# MD029A_CSA.net
KiCad netlist of a schematic drawn in Altium Designer
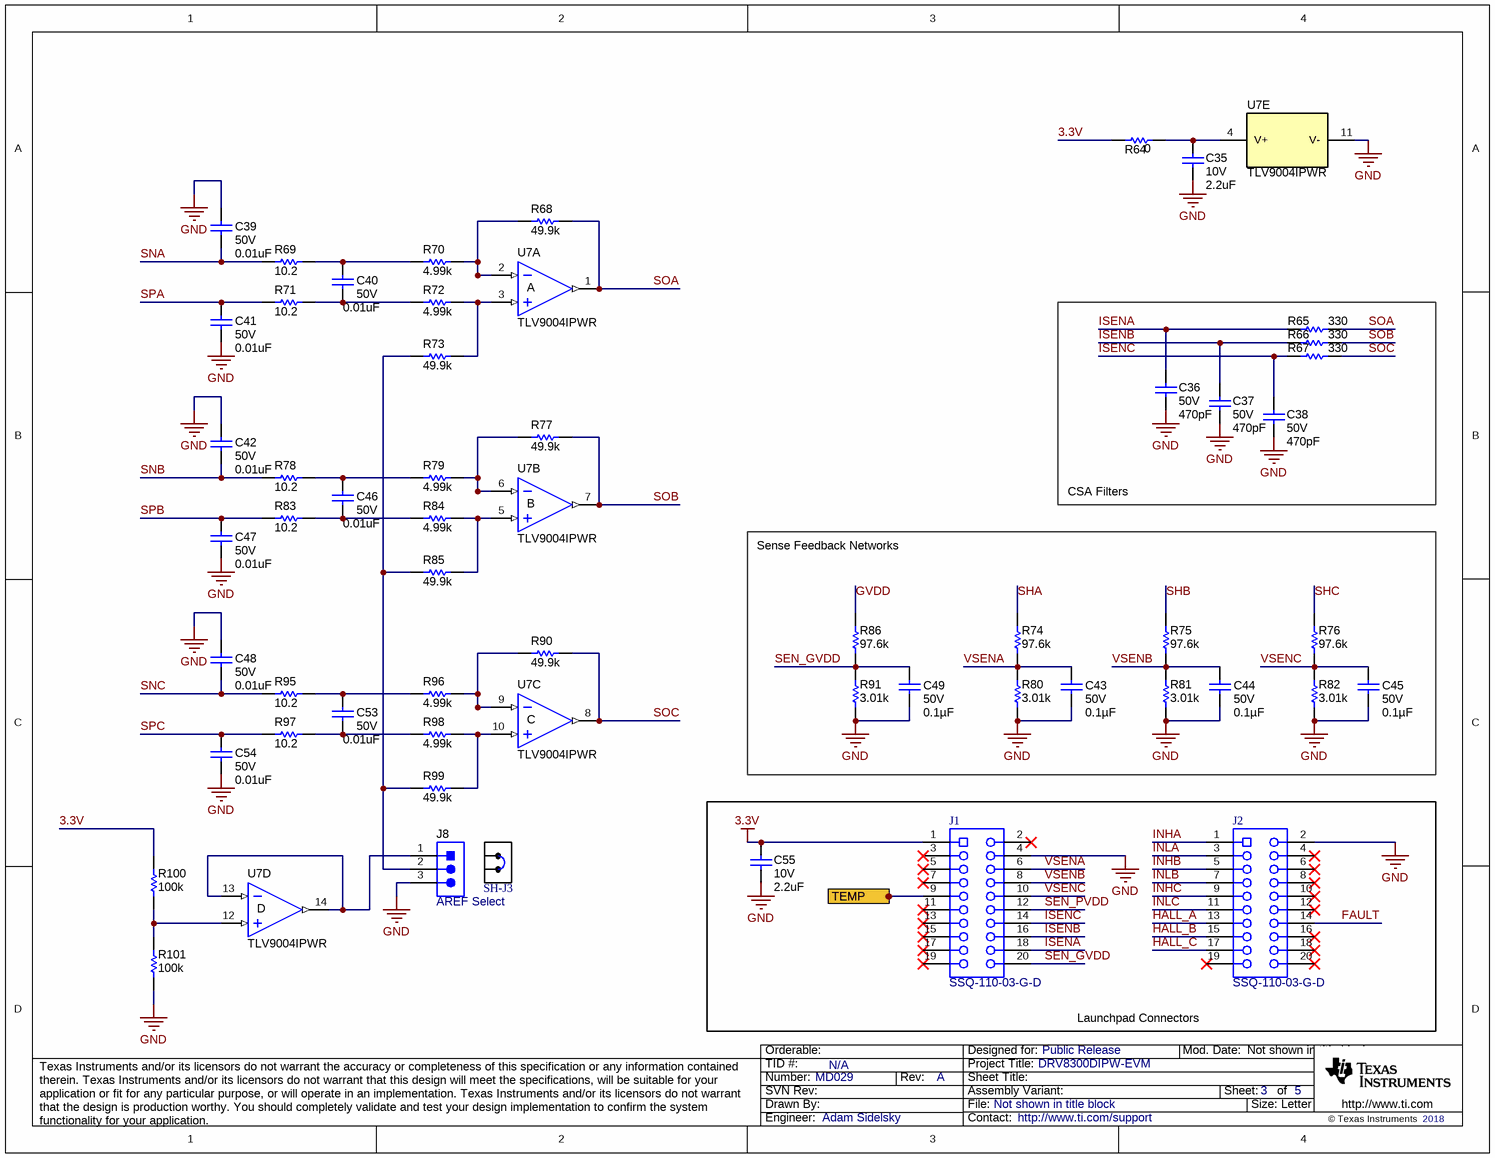
[diagram p0: MD029A_CSA.SchDoc]

(export (version "E")
  (design (tool "Eeschema 10.0.6"))
  (components
    (comp (ref "C35")
      (value "C1005X5R1A225K050BC")
      (footprint "0402L")
      (description "CAP, CERM, 2.2 uF, 10 V, +/- 10%, X5R, 0402")
      (fields
        (field (name "MANUFACTURER") "TDK")
        (field (name "VDC_V") "10V")
        (field (name "VALUEDISPLAYED") "2.2uF")
        (field (name "PUBLISHER") "Texas Instruments")
      )
      (libsource (lib "Altium Vault - TI") (part "Capacitor"))
    )
    (comp (ref "C36")
      (value "C0805C471K5RACTU")
      (footprint "0805L")
      (description "CAP, CERM, 470 pF, 50 V, +/- 10%, X7R, 0805")
      (fields
        (field (name "MANUFACTURER") "Kemet")
        (field (name "VDC_V") "50V")
        (field (name "VALUEDISPLAYED") "470pF")
        (field (name "PUBLISHER") "Texas Instruments")
      )
      (libsource (lib "Altium Vault - TI") (part "Capacitor"))
    )
    (comp (ref "C37")
      (value "C0805C471K5RACTU")
      (footprint "0805L")
      (description "CAP, CERM, 470 pF, 50 V, +/- 10%, X7R, 0805")
      (fields
        (field (name "MANUFACTURER") "Kemet")
        (field (name "VDC_V") "50V")
        (field (name "VALUEDISPLAYED") "470pF")
        (field (name "PUBLISHER") "Texas Instruments")
      )
      (libsource (lib "Altium Vault - TI") (part "Capacitor"))
    )
    (comp (ref "C38")
      (value "C0805C471K5RACTU")
      (footprint "0805L")
      (description "CAP, CERM, 470 pF, 50 V, +/- 10%, X7R, 0805")
      (fields
        (field (name "MANUFACTURER") "Kemet")
        (field (name "VDC_V") "50V")
        (field (name "VALUEDISPLAYED") "470pF")
        (field (name "PUBLISHER") "Texas Instruments")
      )
      (libsource (lib "Altium Vault - TI") (part "Capacitor"))
    )
    (comp (ref "C39")
      (value "GCM188R71H103KA37D")
      (footprint "0603L")
      (description "CAP, CERM, 0.01 uF, 50 V, +/- 10%, X7R, AEC-Q200 Grade 1, 0603")
      (fields
        (field (name "MANUFACTURER") "MuRata")
        (field (name "VDC_V") "50V")
        (field (name "VALUEDISPLAYED") "0.01uF")
        (field (name "PUBLISHER") "Texas Instruments")
      )
      (libsource (lib "Altium Vault - TI") (part "Capacitor"))
    )
    (comp (ref "C40")
      (value "GCM188R71H103KA37D")
      (footprint "0603L")
      (description "CAP, CERM, 0.01 uF, 50 V, +/- 10%, X7R, AEC-Q200 Grade 1, 0603")
      (fields
        (field (name "MANUFACTURER") "MuRata")
        (field (name "VDC_V") "50V")
        (field (name "VALUEDISPLAYED") "0.01uF")
        (field (name "PUBLISHER") "Texas Instruments")
      )
      (libsource (lib "Altium Vault - TI") (part "Capacitor"))
    )
    (comp (ref "C41")
      (value "GCM188R71H103KA37D")
      (footprint "0603L")
      (description "CAP, CERM, 0.01 uF, 50 V, +/- 10%, X7R, AEC-Q200 Grade 1, 0603")
      (fields
        (field (name "MANUFACTURER") "MuRata")
        (field (name "VDC_V") "50V")
        (field (name "VALUEDISPLAYED") "0.01uF")
        (field (name "PUBLISHER") "Texas Instruments")
      )
      (libsource (lib "Altium Vault - TI") (part "Capacitor"))
    )
    (comp (ref "C42")
      (value "GCM188R71H103KA37D")
      (footprint "0603L")
      (description "CAP, CERM, 0.01 uF, 50 V, +/- 10%, X7R, AEC-Q200 Grade 1, 0603")
      (fields
        (field (name "MANUFACTURER") "MuRata")
        (field (name "VDC_V") "50V")
        (field (name "VALUEDISPLAYED") "0.01uF")
        (field (name "PUBLISHER") "Texas Instruments")
      )
      (libsource (lib "Altium Vault - TI") (part "Capacitor"))
    )
    (comp (ref "C43")
      (value "C0603C104K5RACAUTO")
      (footprint "0603L")
      (description "CAP, CERM, 0.1 µF, 50 V,+/- 10%, X7R, AEC-Q200 Grade 1, 0603")
      (fields
        (field (name "MANUFACTURER") "Kemet")
        (field (name "VALUE2") "50V")
        (field (name "VALUEDISPLAYED") "0.1µF")
      )
      (libsource (lib "Altium Vault - TI") (part "Capacitor"))
    )
    (comp (ref "C44")
      (value "C0603C104K5RACAUTO")
      (footprint "0603L")
      (description "CAP, CERM, 0.1 µF, 50 V,+/- 10%, X7R, AEC-Q200 Grade 1, 0603")
      (fields
        (field (name "MANUFACTURER") "Kemet")
        (field (name "VALUE2") "50V")
        (field (name "VALUEDISPLAYED") "0.1µF")
      )
      (libsource (lib "Altium Vault - TI") (part "Capacitor"))
    )
    (comp (ref "C45")
      (value "C0603C104K5RACAUTO")
      (footprint "0603L")
      (description "CAP, CERM, 0.1 µF, 50 V,+/- 10%, X7R, AEC-Q200 Grade 1, 0603")
      (fields
        (field (name "MANUFACTURER") "Kemet")
        (field (name "VALUE2") "50V")
        (field (name "VALUEDISPLAYED") "0.1µF")
      )
      (libsource (lib "Altium Vault - TI") (part "Capacitor"))
    )
    (comp (ref "C46")
      (value "GCM188R71H103KA37D")
      (footprint "0603L")
      (description "CAP, CERM, 0.01 uF, 50 V, +/- 10%, X7R, AEC-Q200 Grade 1, 0603")
      (fields
        (field (name "MANUFACTURER") "MuRata")
        (field (name "VDC_V") "50V")
        (field (name "VALUEDISPLAYED") "0.01uF")
        (field (name "PUBLISHER") "Texas Instruments")
      )
      (libsource (lib "Altium Vault - TI") (part "Capacitor"))
    )
    (comp (ref "C47")
      (value "GCM188R71H103KA37D")
      (footprint "0603L")
      (description "CAP, CERM, 0.01 uF, 50 V, +/- 10%, X7R, AEC-Q200 Grade 1, 0603")
      (fields
        (field (name "MANUFACTURER") "MuRata")
        (field (name "VDC_V") "50V")
        (field (name "VALUEDISPLAYED") "0.01uF")
        (field (name "PUBLISHER") "Texas Instruments")
      )
      (libsource (lib "Altium Vault - TI") (part "Capacitor"))
    )
    (comp (ref "C48")
      (value "GCM188R71H103KA37D")
      (footprint "0603L")
      (description "CAP, CERM, 0.01 uF, 50 V, +/- 10%, X7R, AEC-Q200 Grade 1, 0603")
      (fields
        (field (name "MANUFACTURER") "MuRata")
        (field (name "VDC_V") "50V")
        (field (name "VALUEDISPLAYED") "0.01uF")
        (field (name "PUBLISHER") "Texas Instruments")
      )
      (libsource (lib "Altium Vault - TI") (part "Capacitor"))
    )
    (comp (ref "C49")
      (value "C0603C104K5RACAUTO")
      (footprint "0603L")
      (description "CAP, CERM, 0.1 µF, 50 V,+/- 10%, X7R, AEC-Q200 Grade 1, 0603")
      (fields
        (field (name "MANUFACTURER") "Kemet")
        (field (name "VALUE2") "50V")
        (field (name "VALUEDISPLAYED") "0.1µF")
      )
      (libsource (lib "Altium Vault - TI") (part "Capacitor"))
    )
    (comp (ref "C53")
      (value "GCM188R71H103KA37D")
      (footprint "0603L")
      (description "CAP, CERM, 0.01 uF, 50 V, +/- 10%, X7R, AEC-Q200 Grade 1, 0603")
      (fields
        (field (name "MANUFACTURER") "MuRata")
        (field (name "VDC_V") "50V")
        (field (name "VALUEDISPLAYED") "0.01uF")
        (field (name "PUBLISHER") "Texas Instruments")
      )
      (libsource (lib "Altium Vault - TI") (part "Capacitor"))
    )
    (comp (ref "C54")
      (value "GCM188R71H103KA37D")
      (footprint "0603L")
      (description "CAP, CERM, 0.01 uF, 50 V, +/- 10%, X7R, AEC-Q200 Grade 1, 0603")
      (fields
        (field (name "MANUFACTURER") "MuRata")
        (field (name "VDC_V") "50V")
        (field (name "VALUEDISPLAYED") "0.01uF")
        (field (name "PUBLISHER") "Texas Instruments")
      )
      (libsource (lib "Altium Vault - TI") (part "Capacitor"))
    )
    (comp (ref "C55")
      (value "C1005X5R1A225K050BC")
      (footprint "0402L")
      (description "CAP, CERM, 2.2 uF, 10 V, +/- 10%, X5R, 0402")
      (fields
        (field (name "MANUFACTURER") "TDK")
        (field (name "VDC_V") "10V")
        (field (name "VALUEDISPLAYED") "2.2uF")
        (field (name "PUBLISHER") "Texas Instruments")
      )
      (libsource (lib "Altium Vault - TI") (part "Capacitor"))
    )
    (comp (ref "J1")
      (value "SSQ-110-03-G-D")
      (footprint "Samtec_SSQ-110-03-x-D")
      (description "Receptacle, 2.54mm, 10x2, Gold, TH")
      (fields (field (name "MANUFACTURER") "Samtec") (field (name "PUBLISHER") "Texas Instruments"))
      (libsource (lib "Altium Vault - TI") (part "Receptacle_10x2"))
    )
    (comp (ref "J2")
      (value "SSQ-110-03-G-D")
      (footprint "Samtec_SSQ-110-03-x-D")
      (description "Receptacle, 2.54mm, 10x2, Gold, TH")
      (fields (field (name "MANUFACTURER") "Samtec") (field (name "PUBLISHER") "Texas Instruments"))
      (libsource (lib "Altium Vault - TI") (part "Receptacle_10x2"))
    )
    (comp (ref "J8")
      (value "AREF Select")
      (footprint "WURTH_61300311121")
      (description "Header, 2.54 mm, 3x1, Gold, TH")
      (fields (field (name "MANUFACTURER") "Wurth Elektronik") (field (name "PARTNUMBER") "61300311121"))
      (libsource (lib "Altium Vault - TI") (part "Header_3x1"))
    )
    (comp (ref "R64")
      (value "0")
      (footprint "0603L")
      (description "RES, 0, 5%, 0.1 W, AEC-Q200 Grade 0, 0603")
      (fields (field (name "PARTNUMBER") "CRCW06030000Z0EA") (field (name "MANUFACTURER") "Vishay-Dale"))
      (libsource (lib "Altium Vault - TI") (part "Resistor"))
    )
    (comp (ref "R65")
      (value "CRCW0805330RFKEAC")
      (footprint "0805L")
      (description "RES, 330, 1%, 0.125 W, 0805")
      (fields (field (name "MANUFACTURER") "Vishay-Dale") (field (name "VALUEDISPLAYED") "330"))
      (libsource (lib "Altium Vault - TI") (part "Resistor"))
    )
    (comp (ref "R66")
      (value "CRCW0805330RFKEAC")
      (footprint "0805L")
      (description "RES, 330, 1%, 0.125 W, 0805")
      (fields (field (name "MANUFACTURER") "Vishay-Dale") (field (name "VALUEDISPLAYED") "330"))
      (libsource (lib "Altium Vault - TI") (part "Resistor"))
    )
    (comp (ref "R67")
      (value "CRCW0805330RFKEAC")
      (footprint "0805L")
      (description "RES, 330, 1%, 0.125 W, 0805")
      (fields (field (name "MANUFACTURER") "Vishay-Dale") (field (name "VALUEDISPLAYED") "330"))
      (libsource (lib "Altium Vault - TI") (part "Resistor"))
    )
    (comp (ref "R68")
      (value "CRCW060349K9FKEA")
      (footprint "0603L")
      (description "RES, 49.9 k, 1%, 0.1 W, AEC-Q200 Grade 0, 0603")
      (fields (field (name "MANUFACTURER") "Vishay-Dale") (field (name "VALUEDISPLAYED") "49.9k"))
      (libsource (lib "Altium Vault - TI") (part "Resistor"))
    )
    (comp (ref "R69")
      (value "CRCW060310R2FKEA")
      (footprint "0603L")
      (description "RES, 10.2, 1%, 0.1 W, AEC-Q200 Grade 0, 0603")
      (fields (field (name "MANUFACTURER") "Vishay-Dale") (field (name "VALUEDISPLAYED") "10.2"))
      (libsource (lib "Altium Vault - TI") (part "Resistor"))
    )
    (comp (ref "R70")
      (value "CRCW06034K99FKEA")
      (footprint "0603L")
      (description "RES, 4.99 k, 1%, 0.1 W, AEC-Q200 Grade 0, 0603")
      (fields (field (name "MANUFACTURER") "Vishay-Dale") (field (name "VALUEDISPLAYED") "4.99k"))
      (libsource (lib "Altium Vault - TI") (part "Resistor"))
    )
    (comp (ref "R71")
      (value "CRCW060310R2FKEA")
      (footprint "0603L")
      (description "RES, 10.2, 1%, 0.1 W, AEC-Q200 Grade 0, 0603")
      (fields (field (name "MANUFACTURER") "Vishay-Dale") (field (name "VALUEDISPLAYED") "10.2"))
      (libsource (lib "Altium Vault - TI") (part "Resistor"))
    )
    (comp (ref "R72")
      (value "CRCW06034K99FKEA")
      (footprint "0603L")
      (description "RES, 4.99 k, 1%, 0.1 W, AEC-Q200 Grade 0, 0603")
      (fields (field (name "MANUFACTURER") "Vishay-Dale") (field (name "VALUEDISPLAYED") "4.99k"))
      (libsource (lib "Altium Vault - TI") (part "Resistor"))
    )
    (comp (ref "R73")
      (value "CRCW060349K9FKEA")
      (footprint "0603L")
      (description "RES, 49.9 k, 1%, 0.1 W, AEC-Q200 Grade 0, 0603")
      (fields (field (name "MANUFACTURER") "Vishay-Dale") (field (name "VALUEDISPLAYED") "49.9k"))
      (libsource (lib "Altium Vault - TI") (part "Resistor"))
    )
    (comp (ref "R74")
      (value "CRCW060397K6FKEA")
      (footprint "0603L")
      (description "RES, 97.6 k, 1%, 0.1 W, AEC-Q200 Grade 0, 0603")
      (fields (field (name "MANUFACTURER") "Vishay-Dale") (field (name "VALUEDISPLAYED") "97.6k"))
      (libsource (lib "Altium Vault - TI") (part "Resistor"))
    )
    (comp (ref "R75")
      (value "CRCW060397K6FKEA")
      (footprint "0603L")
      (description "RES, 97.6 k, 1%, 0.1 W, AEC-Q200 Grade 0, 0603")
      (fields (field (name "MANUFACTURER") "Vishay-Dale") (field (name "VALUEDISPLAYED") "97.6k"))
      (libsource (lib "Altium Vault - TI") (part "Resistor"))
    )
    (comp (ref "R76")
      (value "CRCW060397K6FKEA")
      (footprint "0603L")
      (description "RES, 97.6 k, 1%, 0.1 W, AEC-Q200 Grade 0, 0603")
      (fields (field (name "MANUFACTURER") "Vishay-Dale") (field (name "VALUEDISPLAYED") "97.6k"))
      (libsource (lib "Altium Vault - TI") (part "Resistor"))
    )
    (comp (ref "R77")
      (value "CRCW060349K9FKEA")
      (footprint "0603L")
      (description "RES, 49.9 k, 1%, 0.1 W, AEC-Q200 Grade 0, 0603")
      (fields (field (name "MANUFACTURER") "Vishay-Dale") (field (name "VALUEDISPLAYED") "49.9k"))
      (libsource (lib "Altium Vault - TI") (part "Resistor"))
    )
    (comp (ref "R78")
      (value "CRCW060310R2FKEA")
      (footprint "0603L")
      (description "RES, 10.2, 1%, 0.1 W, AEC-Q200 Grade 0, 0603")
      (fields (field (name "MANUFACTURER") "Vishay-Dale") (field (name "VALUEDISPLAYED") "10.2"))
      (libsource (lib "Altium Vault - TI") (part "Resistor"))
    )
    (comp (ref "R79")
      (value "CRCW06034K99FKEA")
      (footprint "0603L")
      (description "RES, 4.99 k, 1%, 0.1 W, AEC-Q200 Grade 0, 0603")
      (fields (field (name "MANUFACTURER") "Vishay-Dale") (field (name "VALUEDISPLAYED") "4.99k"))
      (libsource (lib "Altium Vault - TI") (part "Resistor"))
    )
    (comp (ref "R80")
      (value "CRCW06033K01FKEA")
      (footprint "0603L")
      (description "RES, 3.01 k, 1%, 0.1 W, AEC-Q200 Grade 0, 0603")
      (fields (field (name "MANUFACTURER") "Vishay-Dale") (field (name "VALUEDISPLAYED") "3.01k"))
      (libsource (lib "Altium Vault - TI") (part "Resistor"))
    )
    (comp (ref "R81")
      (value "CRCW06033K01FKEA")
      (footprint "0603L")
      (description "RES, 3.01 k, 1%, 0.1 W, AEC-Q200 Grade 0, 0603")
      (fields (field (name "MANUFACTURER") "Vishay-Dale") (field (name "VALUEDISPLAYED") "3.01k"))
      (libsource (lib "Altium Vault - TI") (part "Resistor"))
    )
    (comp (ref "R82")
      (value "CRCW06033K01FKEA")
      (footprint "0603L")
      (description "RES, 3.01 k, 1%, 0.1 W, AEC-Q200 Grade 0, 0603")
      (fields (field (name "MANUFACTURER") "Vishay-Dale") (field (name "VALUEDISPLAYED") "3.01k"))
      (libsource (lib "Altium Vault - TI") (part "Resistor"))
    )
    (comp (ref "R83")
      (value "CRCW060310R2FKEA")
      (footprint "0603L")
      (description "RES, 10.2, 1%, 0.1 W, AEC-Q200 Grade 0, 0603")
      (fields (field (name "MANUFACTURER") "Vishay-Dale") (field (name "VALUEDISPLAYED") "10.2"))
      (libsource (lib "Altium Vault - TI") (part "Resistor"))
    )
    (comp (ref "R84")
      (value "CRCW06034K99FKEA")
      (footprint "0603L")
      (description "RES, 4.99 k, 1%, 0.1 W, AEC-Q200 Grade 0, 0603")
      (fields (field (name "MANUFACTURER") "Vishay-Dale") (field (name "VALUEDISPLAYED") "4.99k"))
      (libsource (lib "Altium Vault - TI") (part "Resistor"))
    )
    (comp (ref "R85")
      (value "CRCW060349K9FKEA")
      (footprint "0603L")
      (description "RES, 49.9 k, 1%, 0.1 W, AEC-Q200 Grade 0, 0603")
      (fields (field (name "MANUFACTURER") "Vishay-Dale") (field (name "VALUEDISPLAYED") "49.9k"))
      (libsource (lib "Altium Vault - TI") (part "Resistor"))
    )
    (comp (ref "R86")
      (value "CRCW060397K6FKEA")
      (footprint "0603L")
      (description "RES, 97.6 k, 1%, 0.1 W, AEC-Q200 Grade 0, 0603")
      (fields (field (name "MANUFACTURER") "Vishay-Dale") (field (name "VALUEDISPLAYED") "97.6k"))
      (libsource (lib "Altium Vault - TI") (part "Resistor"))
    )
    (comp (ref "R90")
      (value "CRCW060349K9FKEA")
      (footprint "0603L")
      (description "RES, 49.9 k, 1%, 0.1 W, AEC-Q200 Grade 0, 0603")
      (fields (field (name "MANUFACTURER") "Vishay-Dale") (field (name "VALUEDISPLAYED") "49.9k"))
      (libsource (lib "Altium Vault - TI") (part "Resistor"))
    )
    (comp (ref "R91")
      (value "CRCW06033K01FKEA")
      (footprint "0603L")
      (description "RES, 3.01 k, 1%, 0.1 W, AEC-Q200 Grade 0, 0603")
      (fields (field (name "MANUFACTURER") "Vishay-Dale") (field (name "VALUEDISPLAYED") "3.01k"))
      (libsource (lib "Altium Vault - TI") (part "Resistor"))
    )
    (comp (ref "R95")
      (value "CRCW060310R2FKEA")
      (footprint "0603L")
      (description "RES, 10.2, 1%, 0.1 W, AEC-Q200 Grade 0, 0603")
      (fields (field (name "MANUFACTURER") "Vishay-Dale") (field (name "VALUEDISPLAYED") "10.2"))
      (libsource (lib "Altium Vault - TI") (part "Resistor"))
    )
    (comp (ref "R96")
      (value "CRCW06034K99FKEA")
      (footprint "0603L")
      (description "RES, 4.99 k, 1%, 0.1 W, AEC-Q200 Grade 0, 0603")
      (fields (field (name "MANUFACTURER") "Vishay-Dale") (field (name "VALUEDISPLAYED") "4.99k"))
      (libsource (lib "Altium Vault - TI") (part "Resistor"))
    )
    (comp (ref "R97")
      (value "CRCW060310R2FKEA")
      (footprint "0603L")
      (description "RES, 10.2, 1%, 0.1 W, AEC-Q200 Grade 0, 0603")
      (fields (field (name "MANUFACTURER") "Vishay-Dale") (field (name "VALUEDISPLAYED") "10.2"))
      (libsource (lib "Altium Vault - TI") (part "Resistor"))
    )
    (comp (ref "R98")
      (value "CRCW06034K99FKEA")
      (footprint "0603L")
      (description "RES, 4.99 k, 1%, 0.1 W, AEC-Q200 Grade 0, 0603")
      (fields (field (name "MANUFACTURER") "Vishay-Dale") (field (name "VALUEDISPLAYED") "4.99k"))
      (libsource (lib "Altium Vault - TI") (part "Resistor"))
    )
    (comp (ref "R99")
      (value "CRCW060349K9FKEA")
      (footprint "0603L")
      (description "RES, 49.9 k, 1%, 0.1 W, AEC-Q200 Grade 0, 0603")
      (fields (field (name "MANUFACTURER") "Vishay-Dale") (field (name "VALUEDISPLAYED") "49.9k"))
      (libsource (lib "Altium Vault - TI") (part "Resistor"))
    )
    (comp (ref "R100")
      (value "CRCW0603100KFKEA")
      (footprint "0603L")
      (description "RES, 100 k, 1%, 0.1 W, AEC-Q200 Grade 0, 0603")
      (fields (field (name "MANUFACTURER") "Vishay-Dale") (field (name "VALUEDISPLAYED") "100k"))
      (libsource (lib "Altium Vault - TI") (part "Resistor"))
    )
    (comp (ref "R101")
      (value "CRCW0603100KFKEA")
      (footprint "0603L")
      (description "RES, 100 k, 1%, 0.1 W, AEC-Q200 Grade 0, 0603")
      (fields (field (name "MANUFACTURER") "Vishay-Dale") (field (name "VALUEDISPLAYED") "100k"))
      (libsource (lib "Altium Vault - TI") (part "Resistor"))
    )
    (comp (ref "SH-J3")
      (value "SNT-100-BK-G")
      (footprint "SNT-100-BK-G")
      (description "Shunt, 100mil, Gold plated, Black")
      (fields (field (name "ALTERNATE PARTNUMBER") "969102-0000-DA") (field (name "MANUFACTURER") "Samtec"))
      (libsource (lib "Altium Vault - TI") (part "Shunt"))
    )
    (comp (ref "U7")
      (value "TLV9004IPWR")
      (footprint "PW0014A_N")
      (fields (field (name "MANUFACTURER") "Texas Instruments") (field (name "PARTNUMBER") "TLV9004IPWR"))
      (libsource (lib "Altium Vault - TI") (part "OpAmp_Quad"))
    )
  )
  (nets
    (net (code "1") (name "/FAULT") (class "Default")
      (node (ref "J2") (pin "14") (pinfunction "14_14") (pintype "passive"))
    )
    (net (code "2") (name "/GVDD") (class "Default")
      (node (ref "R86") (pin "2") (pinfunction "2_2") (pintype "passive"))
    )
    (net (code "3") (name "/HALL_A") (class "Default")
      (node (ref "J2") (pin "13") (pinfunction "13_13") (pintype "passive"))
    )
    (net (code "4") (name "/HALL_B") (class "Default")
      (node (ref "J2") (pin "15") (pinfunction "15_15") (pintype "passive"))
    )
    (net (code "5") (name "/HALL_C") (class "Default")
      (node (ref "J2") (pin "17") (pinfunction "17_17") (pintype "passive"))
    )
    (net (code "6") (name "/INHA") (class "Default")
      (node (ref "J2") (pin "1") (pinfunction "1_1") (pintype "passive"))
    )
    (net (code "7") (name "/INHB") (class "Default")
      (node (ref "J2") (pin "5") (pinfunction "5_5") (pintype "passive"))
    )
    (net (code "8") (name "/INHC") (class "Default")
      (node (ref "J2") (pin "9") (pinfunction "9_9") (pintype "passive"))
    )
    (net (code "9") (name "/INLA") (class "Default")
      (node (ref "J2") (pin "3") (pinfunction "3_3") (pintype "passive"))
    )
    (net (code "10") (name "/INLB") (class "Default")
      (node (ref "J2") (pin "7") (pinfunction "7_7") (pintype "passive"))
    )
    (net (code "11") (name "/INLC") (class "Default")
      (node (ref "J2") (pin "11") (pinfunction "11_11") (pintype "passive"))
    )
    (net (code "12") (name "/ISENA") (class "Default")
      (node (ref "C36") (pin "1") (pinfunction "1_1") (pintype "passive"))
      (node (ref "J1") (pin "18") (pinfunction "18_18") (pintype "passive"))
      (node (ref "R65") (pin "1") (pinfunction "1_1") (pintype "passive"))
    )
    (net (code "13") (name "/ISENB") (class "Default")
      (node (ref "C37") (pin "1") (pinfunction "1_1") (pintype "passive"))
      (node (ref "J1") (pin "16") (pinfunction "16_16") (pintype "passive"))
      (node (ref "R66") (pin "1") (pinfunction "1_1") (pintype "passive"))
    )
    (net (code "14") (name "/ISENC") (class "Default")
      (node (ref "C38") (pin "1") (pinfunction "1_1") (pintype "passive"))
      (node (ref "J1") (pin "14") (pinfunction "14_14") (pintype "passive"))
      (node (ref "R67") (pin "1") (pinfunction "1_1") (pintype "passive"))
    )
    (net (code "15") (name "/SEN_GVDD") (class "Default")
      (node (ref "C49") (pin "2") (pinfunction "2_2") (pintype "passive"))
      (node (ref "J1") (pin "20") (pinfunction "20_20") (pintype "passive"))
      (node (ref "R86") (pin "1") (pinfunction "1_1") (pintype "passive"))
      (node (ref "R91") (pin "2") (pinfunction "2_2") (pintype "passive"))
    )
    (net (code "16") (name "/SEN_PVDD") (class "Default")
      (node (ref "J1") (pin "12") (pinfunction "12_12") (pintype "passive"))
    )
    (net (code "17") (name "/SHA") (class "Default")
      (node (ref "R74") (pin "2") (pinfunction "2_2") (pintype "passive"))
    )
    (net (code "18") (name "/SHB") (class "Default")
      (node (ref "R75") (pin "2") (pinfunction "2_2") (pintype "passive"))
    )
    (net (code "19") (name "/SHC") (class "Default")
      (node (ref "R76") (pin "2") (pinfunction "2_2") (pintype "passive"))
    )
    (net (code "20") (name "/SNA") (class "Default")
      (node (ref "C39") (pin "2") (pinfunction "2_2") (pintype "passive"))
      (node (ref "R69") (pin "1") (pinfunction "1_1") (pintype "passive"))
    )
    (net (code "21") (name "/SNB") (class "Default")
      (node (ref "C42") (pin "2") (pinfunction "2_2") (pintype "passive"))
      (node (ref "R78") (pin "1") (pinfunction "1_1") (pintype "passive"))
    )
    (net (code "22") (name "/SNC") (class "Default")
      (node (ref "C48") (pin "2") (pinfunction "2_2") (pintype "passive"))
      (node (ref "R95") (pin "1") (pinfunction "1_1") (pintype "passive"))
    )
    (net (code "23") (name "/SOA") (class "Default")
      (node (ref "R65") (pin "2") (pinfunction "2_2") (pintype "passive"))
      (node (ref "R68") (pin "2") (pinfunction "2_2") (pintype "passive"))
      (node (ref "U7") (pin "1") (pinfunction "OUT_1") (pintype "output"))
    )
    (net (code "24") (name "/SOB") (class "Default")
      (node (ref "R66") (pin "2") (pinfunction "2_2") (pintype "passive"))
      (node (ref "R77") (pin "2") (pinfunction "2_2") (pintype "passive"))
      (node (ref "U7") (pin "7") (pinfunction "OUT_7") (pintype "output"))
    )
    (net (code "25") (name "/SOC") (class "Default")
      (node (ref "R67") (pin "2") (pinfunction "2_2") (pintype "passive"))
      (node (ref "R90") (pin "2") (pinfunction "2_2") (pintype "passive"))
      (node (ref "U7") (pin "8") (pinfunction "OUT_8") (pintype "output"))
    )
    (net (code "26") (name "/SPA") (class "Default")
      (node (ref "C41") (pin "1") (pinfunction "1_1") (pintype "passive"))
      (node (ref "R71") (pin "1") (pinfunction "1_1") (pintype "passive"))
    )
    (net (code "27") (name "/SPB") (class "Default")
      (node (ref "C47") (pin "1") (pinfunction "1_1") (pintype "passive"))
      (node (ref "R83") (pin "1") (pinfunction "1_1") (pintype "passive"))
    )
    (net (code "28") (name "/SPC") (class "Default")
      (node (ref "C54") (pin "1") (pinfunction "1_1") (pintype "passive"))
      (node (ref "R97") (pin "1") (pinfunction "1_1") (pintype "passive"))
    )
    (net (code "29") (name "/TEMP") (class "Default")
      (node (ref "J1") (pin "9") (pinfunction "9_9") (pintype "passive"))
    )
    (net (code "30") (name "/VSENA") (class "Default")
      (node (ref "C43") (pin "2") (pinfunction "2_2") (pintype "passive"))
      (node (ref "J1") (pin "6") (pinfunction "6_6") (pintype "passive"))
      (node (ref "R74") (pin "1") (pinfunction "1_1") (pintype "passive"))
      (node (ref "R80") (pin "2") (pinfunction "2_2") (pintype "passive"))
    )
    (net (code "31") (name "/VSENB") (class "Default")
      (node (ref "C44") (pin "2") (pinfunction "2_2") (pintype "passive"))
      (node (ref "J1") (pin "8") (pinfunction "8_8") (pintype "passive"))
      (node (ref "R75") (pin "1") (pinfunction "1_1") (pintype "passive"))
      (node (ref "R81") (pin "2") (pinfunction "2_2") (pintype "passive"))
    )
    (net (code "32") (name "/VSENC") (class "Default")
      (node (ref "C45") (pin "2") (pinfunction "2_2") (pintype "passive"))
      (node (ref "J1") (pin "10") (pinfunction "10_10") (pintype "passive"))
      (node (ref "R76") (pin "1") (pinfunction "1_1") (pintype "passive"))
      (node (ref "R82") (pin "2") (pinfunction "2_2") (pintype "passive"))
    )
    (net (code "33") (name "3.3V") (class "Default")
      (node (ref "C55") (pin "2") (pinfunction "2_2") (pintype "passive"))
      (node (ref "J1") (pin "1") (pinfunction "1_1") (pintype "passive"))
      (node (ref "R100") (pin "2") (pinfunction "2_2") (pintype "passive"))
      (node (ref "R64") (pin "2") (pinfunction "2_2") (pintype "passive"))
    )
    (net (code "34") (name "GND") (class "Default")
      (node (ref "C35") (pin "1") (pinfunction "1_1") (pintype "passive"))
      (node (ref "C36") (pin "2") (pinfunction "2_2") (pintype "passive"))
      (node (ref "C37") (pin "2") (pinfunction "2_2") (pintype "passive"))
      (node (ref "C38") (pin "2") (pinfunction "2_2") (pintype "passive"))
      (node (ref "C39") (pin "1") (pinfunction "1_1") (pintype "passive"))
      (node (ref "C41") (pin "2") (pinfunction "2_2") (pintype "passive"))
      (node (ref "C42") (pin "1") (pinfunction "1_1") (pintype "passive"))
      (node (ref "C43") (pin "1") (pinfunction "1_1") (pintype "passive"))
      (node (ref "C44") (pin "1") (pinfunction "1_1") (pintype "passive"))
      (node (ref "C45") (pin "1") (pinfunction "1_1") (pintype "passive"))
      (node (ref "C47") (pin "2") (pinfunction "2_2") (pintype "passive"))
      (node (ref "C48") (pin "1") (pinfunction "1_1") (pintype "passive"))
      (node (ref "C49") (pin "1") (pinfunction "1_1") (pintype "passive"))
      (node (ref "C54") (pin "2") (pinfunction "2_2") (pintype "passive"))
      (node (ref "C55") (pin "1") (pinfunction "1_1") (pintype "passive"))
      (node (ref "J1") (pin "4") (pinfunction "4_4") (pintype "passive"))
      (node (ref "J2") (pin "2") (pinfunction "2_2") (pintype "passive"))
      (node (ref "J8") (pin "3") (pinfunction "3_3") (pintype "passive"))
      (node (ref "R101") (pin "1") (pinfunction "1_1") (pintype "passive"))
      (node (ref "R80") (pin "1") (pinfunction "1_1") (pintype "passive"))
      (node (ref "R81") (pin "1") (pinfunction "1_1") (pintype "passive"))
      (node (ref "R82") (pin "1") (pinfunction "1_1") (pintype "passive"))
      (node (ref "R91") (pin "1") (pinfunction "1_1") (pintype "passive"))
      (node (ref "U7") (pin "11") (pinfunction "V-_11") (pintype "power_in"))
    )
    (net (code "35") (name "Net-(C40-Pad1)") (class "Default")
      (node (ref "C40") (pin "1") (pinfunction "1_1") (pintype "passive"))
      (node (ref "R69") (pin "2") (pinfunction "2_2") (pintype "passive"))
      (node (ref "R70") (pin "1") (pinfunction "1_1") (pintype "passive"))
    )
    (net (code "36") (name "Net-(C40-Pad2)") (class "Default")
      (node (ref "C40") (pin "2") (pinfunction "2_2") (pintype "passive"))
      (node (ref "R71") (pin "2") (pinfunction "2_2") (pintype "passive"))
      (node (ref "R72") (pin "1") (pinfunction "1_1") (pintype "passive"))
    )
    (net (code "37") (name "Net-(C46-Pad1)") (class "Default")
      (node (ref "C46") (pin "1") (pinfunction "1_1") (pintype "passive"))
      (node (ref "R78") (pin "2") (pinfunction "2_2") (pintype "passive"))
      (node (ref "R79") (pin "1") (pinfunction "1_1") (pintype "passive"))
    )
    (net (code "38") (name "Net-(C46-Pad2)") (class "Default")
      (node (ref "C46") (pin "2") (pinfunction "2_2") (pintype "passive"))
      (node (ref "R83") (pin "2") (pinfunction "2_2") (pintype "passive"))
      (node (ref "R84") (pin "1") (pinfunction "1_1") (pintype "passive"))
    )
    (net (code "39") (name "Net-(C53-Pad1)") (class "Default")
      (node (ref "C53") (pin "1") (pinfunction "1_1") (pintype "passive"))
      (node (ref "R95") (pin "2") (pinfunction "2_2") (pintype "passive"))
      (node (ref "R96") (pin "1") (pinfunction "1_1") (pintype "passive"))
    )
    (net (code "40") (name "Net-(C53-Pad2)") (class "Default")
      (node (ref "C53") (pin "2") (pinfunction "2_2") (pintype "passive"))
      (node (ref "R97") (pin "2") (pinfunction "2_2") (pintype "passive"))
      (node (ref "R98") (pin "1") (pinfunction "1_1") (pintype "passive"))
    )
    (net (code "41") (name "Net-(J8-Pad2)") (class "Default")
      (node (ref "J8") (pin "2") (pinfunction "2_2") (pintype "passive"))
      (node (ref "R73") (pin "2") (pinfunction "2_2") (pintype "passive"))
      (node (ref "R85") (pin "2") (pinfunction "2_2") (pintype "passive"))
      (node (ref "R99") (pin "2") (pinfunction "2_2") (pintype "passive"))
    )
    (net (code "42") (name "Net-(U7A-IN+)") (class "Default")
      (node (ref "R72") (pin "2") (pinfunction "2_2") (pintype "passive"))
      (node (ref "R73") (pin "1") (pinfunction "1_1") (pintype "passive"))
      (node (ref "U7") (pin "3") (pinfunction "IN+_3") (pintype "input"))
    )
    (net (code "43") (name "Net-(U7A-IN-)") (class "Default")
      (node (ref "R68") (pin "1") (pinfunction "1_1") (pintype "passive"))
      (node (ref "R70") (pin "2") (pinfunction "2_2") (pintype "passive"))
      (node (ref "U7") (pin "2") (pinfunction "IN-_2") (pintype "input"))
    )
    (net (code "44") (name "Net-(U7B-IN+)") (class "Default")
      (node (ref "R84") (pin "2") (pinfunction "2_2") (pintype "passive"))
      (node (ref "R85") (pin "1") (pinfunction "1_1") (pintype "passive"))
      (node (ref "U7") (pin "5") (pinfunction "IN+_5") (pintype "input"))
    )
    (net (code "45") (name "Net-(U7B-IN-)") (class "Default")
      (node (ref "R77") (pin "1") (pinfunction "1_1") (pintype "passive"))
      (node (ref "R79") (pin "2") (pinfunction "2_2") (pintype "passive"))
      (node (ref "U7") (pin "6") (pinfunction "IN-_6") (pintype "input"))
    )
    (net (code "46") (name "Net-(U7C-IN+)") (class "Default")
      (node (ref "R98") (pin "2") (pinfunction "2_2") (pintype "passive"))
      (node (ref "R99") (pin "1") (pinfunction "1_1") (pintype "passive"))
      (node (ref "U7") (pin "10") (pinfunction "IN+_10") (pintype "input"))
    )
    (net (code "47") (name "Net-(U7C-IN-)") (class "Default")
      (node (ref "R90") (pin "1") (pinfunction "1_1") (pintype "passive"))
      (node (ref "R96") (pin "2") (pinfunction "2_2") (pintype "passive"))
      (node (ref "U7") (pin "9") (pinfunction "IN-_9") (pintype "input"))
    )
    (net (code "48") (name "Net-(U7D-IN+)") (class "Default")
      (node (ref "R100") (pin "1") (pinfunction "1_1") (pintype "passive"))
      (node (ref "R101") (pin "2") (pinfunction "2_2") (pintype "passive"))
      (node (ref "U7") (pin "12") (pinfunction "IN+_12") (pintype "input"))
    )
    (net (code "49") (name "Net-(U7D-IN-)") (class "Default")
      (node (ref "J8") (pin "1") (pinfunction "1_1") (pintype "passive"))
      (node (ref "U7") (pin "13") (pinfunction "IN-_13") (pintype "input"))
      (node (ref "U7") (pin "14") (pinfunction "OUT_14") (pintype "output"))
    )
    (net (code "50") (name "Net-(U7E-V+)") (class "Default")
      (node (ref "C35") (pin "2") (pinfunction "2_2") (pintype "passive"))
      (node (ref "R64") (pin "1") (pinfunction "1_1") (pintype "passive"))
      (node (ref "U7") (pin "4") (pinfunction "V+_4") (pintype "power_in"))
    )
    (net (code "51") (name "unconnected-(J1-Pad2)") (class "Default")
      (node (ref "J1") (pin "2") (pinfunction "2_2") (pintype "passive+no_connect"))
    )
    (net (code "52") (name "unconnected-(J1-Pad3)") (class "Default")
      (node (ref "J1") (pin "3") (pinfunction "3_3") (pintype "passive+no_connect"))
    )
    (net (code "53") (name "unconnected-(J1-Pad5)") (class "Default")
      (node (ref "J1") (pin "5") (pinfunction "5_5") (pintype "passive+no_connect"))
    )
    (net (code "54") (name "unconnected-(J1-Pad7)") (class "Default")
      (node (ref "J1") (pin "7") (pinfunction "7_7") (pintype "passive+no_connect"))
    )
    (net (code "55") (name "unconnected-(J1-Pad11)") (class "Default")
      (node (ref "J1") (pin "11") (pinfunction "11_11") (pintype "passive+no_connect"))
    )
    (net (code "56") (name "unconnected-(J1-Pad13)") (class "Default")
      (node (ref "J1") (pin "13") (pinfunction "13_13") (pintype "passive+no_connect"))
    )
    (net (code "57") (name "unconnected-(J1-Pad15)") (class "Default")
      (node (ref "J1") (pin "15") (pinfunction "15_15") (pintype "passive+no_connect"))
    )
    (net (code "58") (name "unconnected-(J1-Pad17)") (class "Default")
      (node (ref "J1") (pin "17") (pinfunction "17_17") (pintype "passive+no_connect"))
    )
    (net (code "59") (name "unconnected-(J1-Pad19)") (class "Default")
      (node (ref "J1") (pin "19") (pinfunction "19_19") (pintype "passive+no_connect"))
    )
    (net (code "60") (name "unconnected-(J2-Pad4)") (class "Default")
      (node (ref "J2") (pin "4") (pinfunction "4_4") (pintype "passive+no_connect"))
    )
    (net (code "61") (name "unconnected-(J2-Pad6)") (class "Default")
      (node (ref "J2") (pin "6") (pinfunction "6_6") (pintype "passive+no_connect"))
    )
    (net (code "62") (name "unconnected-(J2-Pad8)") (class "Default")
      (node (ref "J2") (pin "8") (pinfunction "8_8") (pintype "passive+no_connect"))
    )
    (net (code "63") (name "unconnected-(J2-Pad10)") (class "Default")
      (node (ref "J2") (pin "10") (pinfunction "10_10") (pintype "passive+no_connect"))
    )
    (net (code "64") (name "unconnected-(J2-Pad12)") (class "Default")
      (node (ref "J2") (pin "12") (pinfunction "12_12") (pintype "passive+no_connect"))
    )
    (net (code "65") (name "unconnected-(J2-Pad16)") (class "Default")
      (node (ref "J2") (pin "16") (pinfunction "16_16") (pintype "passive+no_connect"))
    )
    (net (code "66") (name "unconnected-(J2-Pad18)") (class "Default")
      (node (ref "J2") (pin "18") (pinfunction "18_18") (pintype "passive+no_connect"))
    )
    (net (code "67") (name "unconnected-(J2-Pad19)") (class "Default")
      (node (ref "J2") (pin "19") (pinfunction "19_19") (pintype "passive+no_connect"))
    )
    (net (code "68") (name "unconnected-(J2-Pad20)") (class "Default")
      (node (ref "J2") (pin "20") (pinfunction "20_20") (pintype "passive+no_connect"))
    )
  )
)
